# WattMeter-PowerSocket-Controller_V0_100.net
KiCad netlist of a schematic drawn in EAGLE
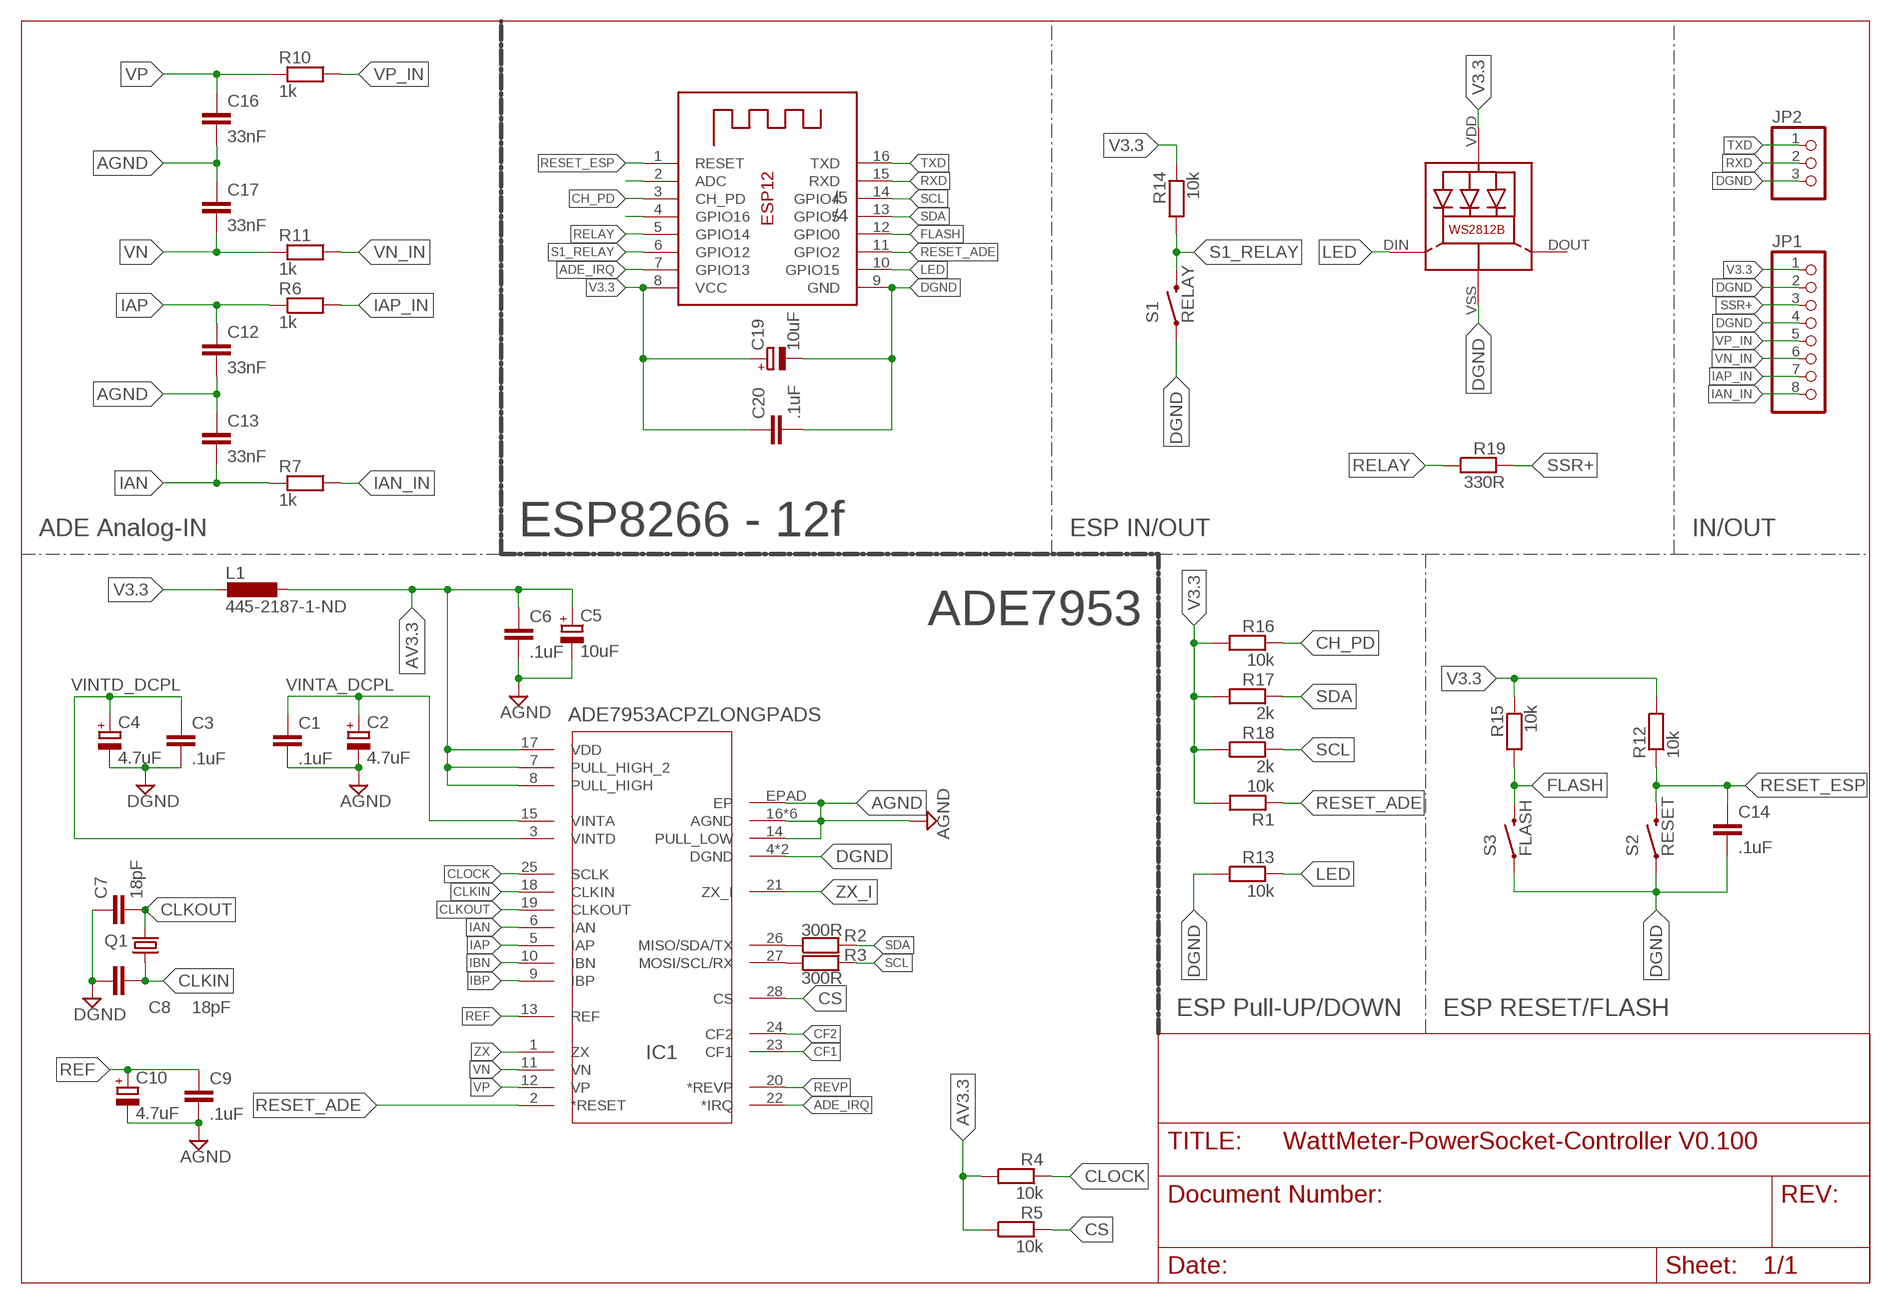
[diagram p0: schematic, sheet 1]

(export (version "E")
  (design (tool "Eeschema 10.0.6"))
  (components
    (comp (ref "C1")
      (value ".1uF")
      (footprint "eagle-import:C0805K@1")
      (libsource (lib "eagle-import") (part "C-EUC0805K"))
    )
    (comp (ref "C2")
      (value "4.7uF")
      (footprint "eagle-import:A_3216-18R")
      (libsource (lib "eagle-import") (part "CPOL-EUA/3216-18R"))
    )
    (comp (ref "C3")
      (value ".1uF")
      (footprint "eagle-import:C0805K@1")
      (libsource (lib "eagle-import") (part "C-EUC0805K"))
    )
    (comp (ref "C4")
      (value "4.7uF")
      (footprint "eagle-import:A_3216-18R")
      (libsource (lib "eagle-import") (part "CPOL-EUA/3216-18R"))
    )
    (comp (ref "C5")
      (value "10uF")
      (footprint "eagle-import:A_3216-18R")
      (libsource (lib "eagle-import") (part "CPOL-EUA/3216-18R"))
    )
    (comp (ref "C6")
      (value ".1uF")
      (footprint "eagle-import:C0805K@1")
      (libsource (lib "eagle-import") (part "C-EUC0805K"))
    )
    (comp (ref "C7")
      (value "18pF")
      (footprint "eagle-import:C0805K@1")
      (libsource (lib "eagle-import") (part "C-EUC0805K"))
    )
    (comp (ref "C8")
      (value "18pF")
      (footprint "eagle-import:C0805K@1")
      (libsource (lib "eagle-import") (part "C-EUC0805K"))
    )
    (comp (ref "C9")
      (value ".1uF")
      (footprint "eagle-import:C0805K@1")
      (libsource (lib "eagle-import") (part "C-EUC0805K"))
    )
    (comp (ref "C10")
      (value "4.7uF")
      (footprint "eagle-import:A_3216-18R")
      (libsource (lib "eagle-import") (part "CPOL-EUA/3216-18R"))
    )
    (comp (ref "C12")
      (value "33nF")
      (footprint "eagle-import:C0805K@1")
      (libsource (lib "eagle-import") (part "C-EUC0805K"))
    )
    (comp (ref "C13")
      (value "33nF")
      (footprint "eagle-import:C0805K@1")
      (libsource (lib "eagle-import") (part "C-EUC0805K"))
    )
    (comp (ref "C14")
      (value ".1uF")
      (footprint "eagle-import:C0805K@1")
      (libsource (lib "eagle-import") (part "C-EUC0805K"))
    )
    (comp (ref "C16")
      (value "33nF")
      (footprint "eagle-import:C0805K@1")
      (libsource (lib "eagle-import") (part "C-EUC0805K"))
    )
    (comp (ref "C17")
      (value "33nF")
      (footprint "eagle-import:C0805K@1")
      (libsource (lib "eagle-import") (part "C-EUC0805K"))
    )
    (comp (ref "C19")
      (value "10uF")
      (footprint "eagle-import:A_3216-18R")
      (libsource (lib "eagle-import") (part "CPOL-EUA/3216-18R"))
    )
    (comp (ref "C20")
      (value ".1uF")
      (footprint "eagle-import:C0805K@1")
      (libsource (lib "eagle-import") (part "C-EUC0805K"))
    )
    (comp (ref "IC1")
      (value "ADE7953ACPZLONGPADS")
      (footprint "eagle-import:VQFN-28-D")
      (libsource (lib "eagle-import") (part "ADE7953ACPZ5.0"))
    )
    (comp (ref "JP1")
      (value "PINHD-1X8")
      (footprint "eagle-import:1X08")
      (libsource (lib "eagle-import") (part "PINHD-1X8"))
    )
    (comp (ref "JP2")
      (value "PINHD-1X3")
      (footprint "eagle-import:1X03")
      (libsource (lib "eagle-import") (part "PINHD-1X3"))
    )
    (comp (ref "L1")
      (value "445-2187-1-ND")
      (footprint "eagle-import:L2012C")
      (libsource (lib "eagle-import") (part "L-EUL2012C"))
    )
    (comp (ref "LED1")
      (value "WS2812B")
      (footprint "eagle-import:WS2812B")
      (libsource (lib "eagle-import") (part "WS2812B"))
    )
    (comp (ref "Q1")
      (value "535-10200-1-ND")
      (footprint "eagle-import:SM49")
      (libsource (lib "eagle-import") (part "CRYSTALSM49"))
    )
    (comp (ref "R1")
      (value "10k")
      (footprint "eagle-import:R0805@1")
      (libsource (lib "eagle-import") (part "R-US_R0805"))
    )
    (comp (ref "R2")
      (value "300R")
      (footprint "eagle-import:R0805@1")
      (libsource (lib "eagle-import") (part "R-US_R0805"))
    )
    (comp (ref "R3")
      (value "300R")
      (footprint "eagle-import:R0805@1")
      (libsource (lib "eagle-import") (part "R-US_R0805"))
    )
    (comp (ref "R4")
      (value "10k")
      (footprint "eagle-import:R0805@1")
      (libsource (lib "eagle-import") (part "R-US_R0805"))
    )
    (comp (ref "R5")
      (value "10k")
      (footprint "eagle-import:R0805@1")
      (libsource (lib "eagle-import") (part "R-US_R0805"))
    )
    (comp (ref "R6")
      (value "1k")
      (footprint "eagle-import:R0805@1")
      (libsource (lib "eagle-import") (part "R-US_R0805"))
    )
    (comp (ref "R7")
      (value "1k")
      (footprint "eagle-import:R0805@1")
      (libsource (lib "eagle-import") (part "R-US_R0805"))
    )
    (comp (ref "R10")
      (value "1k")
      (footprint "eagle-import:R0805@1")
      (libsource (lib "eagle-import") (part "R-US_R0805"))
    )
    (comp (ref "R11")
      (value "1k")
      (footprint "eagle-import:R0805@1")
      (libsource (lib "eagle-import") (part "R-US_R0805"))
    )
    (comp (ref "R12")
      (value "10k")
      (footprint "eagle-import:R0805@1")
      (libsource (lib "eagle-import") (part "R-US_R0805"))
    )
    (comp (ref "R13")
      (value "10k")
      (footprint "eagle-import:R0805@1")
      (libsource (lib "eagle-import") (part "R-US_R0805"))
    )
    (comp (ref "R14")
      (value "10k")
      (footprint "eagle-import:R0805@1")
      (libsource (lib "eagle-import") (part "R-US_R0805"))
    )
    (comp (ref "R15")
      (value "10k")
      (footprint "eagle-import:R0805@1")
      (libsource (lib "eagle-import") (part "R-US_R0805"))
    )
    (comp (ref "R16")
      (value "10k")
      (footprint "eagle-import:R0805@1")
      (libsource (lib "eagle-import") (part "R-US_R0805"))
    )
    (comp (ref "R17")
      (value "2k")
      (footprint "eagle-import:R0805@1")
      (libsource (lib "eagle-import") (part "R-US_R0805"))
    )
    (comp (ref "R18")
      (value "2k")
      (footprint "eagle-import:R0805@1")
      (libsource (lib "eagle-import") (part "R-US_R0805"))
    )
    (comp (ref "R19")
      (value "330R")
      (footprint "eagle-import:R0805@1")
      (libsource (lib "eagle-import") (part "R-US_R0805"))
    )
    (comp (ref "S1")
      (value "RELAY")
      (footprint "eagle-import:TACTILE-SWITCH-SMD")
      (libsource (lib "eagle-import") (part "SWITCH-MOMENTARY-2SMD"))
    )
    (comp (ref "S2")
      (value "RESET")
      (footprint "eagle-import:TACTILE-SWITCH-1101NE")
      (libsource (lib "eagle-import") (part "SWITCH-MOMENTARY-2SMD-1101NE"))
    )
    (comp (ref "S3")
      (value "FLASH")
      (footprint "eagle-import:TACTILE-SWITCH-1101NE")
      (libsource (lib "eagle-import") (part "SWITCH-MOMENTARY-2SMD-1101NE"))
    )
    (comp (ref "X1")
      (value "ESP-12")
      (footprint "eagle-import:ESP-12")
      (libsource (lib "eagle-import") (part "ESP-12"))
    )
  )
  (nets
    (net (code "1") (name "/VINTA_DCPL") (class "Default")
      (node (ref "C1") (pin "1") (pinfunction "1_1") (pintype "passive"))
      (node (ref "C2") (pin "+") (pinfunction "+_+") (pintype "passive"))
      (node (ref "IC1") (pin "15") (pinfunction "VINTA_15") (pintype "passive"))
    )
    (net (code "2") (name "/VINTD_DCPL") (class "Default")
      (node (ref "C3") (pin "1") (pinfunction "1_1") (pintype "passive"))
      (node (ref "C4") (pin "+") (pinfunction "+_+") (pintype "passive"))
      (node (ref "IC1") (pin "3") (pinfunction "VINTD_3") (pintype "passive"))
    )
    (net (code "3") (name "ADE_IRQ") (class "Default")
      (node (ref "IC1") (pin "22") (pinfunction "*IRQ_22") (pintype "passive"))
      (node (ref "X1") (pin "7") (pinfunction "GPIO13_7") (pintype "bidirectional"))
    )
    (net (code "4") (name "AGND") (class "Default")
      (node (ref "C1") (pin "2") (pinfunction "2_2") (pintype "passive"))
      (node (ref "C10") (pin "-") (pinfunction "-_-") (pintype "passive"))
      (node (ref "C12") (pin "2") (pinfunction "2_2") (pintype "passive"))
      (node (ref "C13") (pin "1") (pinfunction "1_1") (pintype "passive"))
      (node (ref "C16") (pin "2") (pinfunction "2_2") (pintype "passive"))
      (node (ref "C17") (pin "1") (pinfunction "1_1") (pintype "passive"))
      (node (ref "C2") (pin "-") (pinfunction "-_-") (pintype "passive"))
      (node (ref "C5") (pin "-") (pinfunction "-_-") (pintype "passive"))
      (node (ref "C6") (pin "2") (pinfunction "2_2") (pintype "passive"))
      (node (ref "C9") (pin "2") (pinfunction "2_2") (pintype "passive"))
      (node (ref "IC1") (pin "14") (pinfunction "PULL_LOW_14") (pintype "passive"))
      (node (ref "IC1") (pin "16") (pinfunction "AGND_16") (pintype "passive"))
      (node (ref "IC1") (pin "29") (pinfunction "AGND_29") (pintype "passive"))
      (node (ref "IC1") (pin "30") (pinfunction "AGND_30") (pintype "passive"))
      (node (ref "IC1") (pin "31") (pinfunction "AGND_31") (pintype "passive"))
      (node (ref "IC1") (pin "32") (pinfunction "AGND_32") (pintype "passive"))
      (node (ref "IC1") (pin "EPAD") (pinfunction "EP_EPAD") (pintype "passive"))
      (node (ref "IC1") (pin "_AGND") (pinfunction "AGND__AGND") (pintype "passive"))
    )
    (net (code "5") (name "AV3.3") (class "Default")
      (node (ref "C5") (pin "+") (pinfunction "+_+") (pintype "passive"))
      (node (ref "C6") (pin "1") (pinfunction "1_1") (pintype "passive"))
      (node (ref "IC1") (pin "17") (pinfunction "VDD_17") (pintype "passive"))
      (node (ref "IC1") (pin "7") (pinfunction "PULL_HIGH_2_7") (pintype "passive"))
      (node (ref "IC1") (pin "8") (pinfunction "PULL_HIGH_8") (pintype "passive"))
      (node (ref "L1") (pin "1") (pinfunction "1_1") (pintype "passive"))
      (node (ref "R4") (pin "2") (pinfunction "2_2") (pintype "passive"))
      (node (ref "R5") (pin "2") (pinfunction "2_2") (pintype "passive"))
    )
    (net (code "6") (name "CF1") (class "Default")
      (node (ref "IC1") (pin "23") (pinfunction "CF1_23") (pintype "passive"))
    )
    (net (code "7") (name "CF2") (class "Default")
      (node (ref "IC1") (pin "24") (pinfunction "CF2_24") (pintype "passive"))
    )
    (net (code "8") (name "CH_PD") (class "Default")
      (node (ref "R16") (pin "1") (pinfunction "1_1") (pintype "passive"))
      (node (ref "X1") (pin "3") (pinfunction "CH_PD_3") (pintype "input"))
    )
    (net (code "9") (name "CLKIN") (class "Default")
      (node (ref "C8") (pin "2") (pinfunction "2_2") (pintype "passive"))
      (node (ref "IC1") (pin "18") (pinfunction "CLKIN_18") (pintype "passive"))
      (node (ref "Q1") (pin "1") (pinfunction "1_1") (pintype "passive"))
    )
    (net (code "10") (name "CLKOUT") (class "Default")
      (node (ref "C7") (pin "2") (pinfunction "2_2") (pintype "passive"))
      (node (ref "IC1") (pin "19") (pinfunction "CLKOUT_19") (pintype "passive"))
      (node (ref "Q1") (pin "2") (pinfunction "2_2") (pintype "passive"))
    )
    (net (code "11") (name "CLOCK") (class "Default")
      (node (ref "IC1") (pin "25") (pinfunction "SCLK_25") (pintype "passive"))
      (node (ref "R4") (pin "1") (pinfunction "1_1") (pintype "passive"))
    )
    (net (code "12") (name "CS") (class "Default")
      (node (ref "IC1") (pin "28") (pinfunction "CS_28") (pintype "passive"))
      (node (ref "R5") (pin "1") (pinfunction "1_1") (pintype "passive"))
    )
    (net (code "13") (name "DGND") (class "Default")
      (node (ref "C14") (pin "2") (pinfunction "2_2") (pintype "passive"))
      (node (ref "C19") (pin "-") (pinfunction "-_-") (pintype "passive"))
      (node (ref "C20") (pin "2") (pinfunction "2_2") (pintype "passive"))
      (node (ref "C3") (pin "2") (pinfunction "2_2") (pintype "passive"))
      (node (ref "C4") (pin "-") (pinfunction "-_-") (pintype "passive"))
      (node (ref "C7") (pin "1") (pinfunction "1_1") (pintype "passive"))
      (node (ref "C8") (pin "1") (pinfunction "1_1") (pintype "passive"))
      (node (ref "IC1") (pin "4") (pinfunction "DGND_4") (pintype "passive"))
      (node (ref "IC1") (pin "_DGND") (pinfunction "DGND__DGND") (pintype "passive"))
      (node (ref "JP1") (pin "2") (pinfunction "2_2") (pintype "passive"))
      (node (ref "JP1") (pin "4") (pinfunction "4_4") (pintype "passive"))
      (node (ref "JP2") (pin "3") (pinfunction "3_3") (pintype "passive"))
      (node (ref "LED1") (pin "VSS") (pinfunction "GND_VSS") (pintype "power_in"))
      (node (ref "R13") (pin "2") (pinfunction "2_2") (pintype "passive"))
      (node (ref "S1") (pin "1") (pinfunction "1_1") (pintype "passive"))
      (node (ref "S2") (pin "1") (pinfunction "1_1") (pintype "passive"))
      (node (ref "S3") (pin "1") (pinfunction "1_1") (pintype "passive"))
      (node (ref "X1") (pin "9") (pinfunction "GND_9") (pintype "power_in"))
    )
    (net (code "14") (name "FLASH") (class "Default")
      (node (ref "R15") (pin "2") (pinfunction "2_2") (pintype "passive"))
      (node (ref "S3") (pin "2") (pinfunction "2_2") (pintype "passive"))
      (node (ref "X1") (pin "12") (pinfunction "GPIO0_12") (pintype "bidirectional"))
    )
    (net (code "15") (name "IAN") (class "Default")
      (node (ref "C13") (pin "2") (pinfunction "2_2") (pintype "passive"))
      (node (ref "IC1") (pin "6") (pinfunction "IAN_6") (pintype "passive"))
      (node (ref "R7") (pin "1") (pinfunction "1_1") (pintype "passive"))
    )
    (net (code "16") (name "IAN_IN") (class "Default")
      (node (ref "JP1") (pin "8") (pinfunction "8_8") (pintype "passive"))
      (node (ref "R7") (pin "2") (pinfunction "2_2") (pintype "passive"))
    )
    (net (code "17") (name "IAP") (class "Default")
      (node (ref "C12") (pin "1") (pinfunction "1_1") (pintype "passive"))
      (node (ref "IC1") (pin "5") (pinfunction "IAP_5") (pintype "passive"))
      (node (ref "R6") (pin "1") (pinfunction "1_1") (pintype "passive"))
    )
    (net (code "18") (name "IAP_IN") (class "Default")
      (node (ref "JP1") (pin "7") (pinfunction "7_7") (pintype "passive"))
      (node (ref "R6") (pin "2") (pinfunction "2_2") (pintype "passive"))
    )
    (net (code "19") (name "IBN") (class "Default")
      (node (ref "IC1") (pin "10") (pinfunction "IBN_10") (pintype "passive"))
    )
    (net (code "20") (name "IBP") (class "Default")
      (node (ref "IC1") (pin "9") (pinfunction "IBP_9") (pintype "passive"))
    )
    (net (code "21") (name "LED") (class "Default")
      (node (ref "LED1") (pin "DIN") (pinfunction "DI_DIN") (pintype "input"))
      (node (ref "R13") (pin "1") (pinfunction "1_1") (pintype "passive"))
      (node (ref "X1") (pin "10") (pinfunction "GPIO15_10") (pintype "bidirectional"))
    )
    (net (code "22") (name "Net-(IC1-MISO{slash}SDA{slash}TX)") (class "Default")
      (node (ref "IC1") (pin "26") (pinfunction "MISO/SDA/TX_26") (pintype "passive"))
      (node (ref "R2") (pin "1") (pinfunction "1_1") (pintype "passive"))
    )
    (net (code "23") (name "Net-(IC1-MOSI{slash}SCL{slash}RX)") (class "Default")
      (node (ref "IC1") (pin "27") (pinfunction "MOSI/SCL/RX_27") (pintype "passive"))
      (node (ref "R3") (pin "1") (pinfunction "1_1") (pintype "passive"))
    )
    (net (code "24") (name "REF") (class "Default")
      (node (ref "C10") (pin "+") (pinfunction "+_+") (pintype "passive"))
      (node (ref "C9") (pin "1") (pinfunction "1_1") (pintype "passive"))
      (node (ref "IC1") (pin "13") (pinfunction "REF_13") (pintype "passive"))
    )
    (net (code "25") (name "RELAY") (class "Default")
      (node (ref "R19") (pin "2") (pinfunction "2_2") (pintype "passive"))
      (node (ref "X1") (pin "5") (pinfunction "GPIO14_5") (pintype "bidirectional"))
    )
    (net (code "26") (name "RESET_ADE") (class "Default")
      (node (ref "IC1") (pin "2") (pinfunction "*RESET_2") (pintype "passive"))
      (node (ref "R1") (pin "1") (pinfunction "1_1") (pintype "passive"))
      (node (ref "X1") (pin "11") (pinfunction "GPIO2_11") (pintype "bidirectional"))
    )
    (net (code "27") (name "RESET_ESP") (class "Default")
      (node (ref "C14") (pin "1") (pinfunction "1_1") (pintype "passive"))
      (node (ref "R12") (pin "1") (pinfunction "1_1") (pintype "passive"))
      (node (ref "S2") (pin "2") (pinfunction "2_2") (pintype "passive"))
      (node (ref "X1") (pin "1") (pinfunction "RESET_1") (pintype "input"))
    )
    (net (code "28") (name "REVP") (class "Default")
      (node (ref "IC1") (pin "20") (pinfunction "*REVP_20") (pintype "passive"))
    )
    (net (code "29") (name "RXD") (class "Default")
      (node (ref "JP2") (pin "2") (pinfunction "2_2") (pintype "passive"))
      (node (ref "X1") (pin "15") (pinfunction "RXD_15") (pintype "input"))
    )
    (net (code "30") (name "S1_RELAY") (class "Default")
      (node (ref "R14") (pin "2") (pinfunction "2_2") (pintype "passive"))
      (node (ref "S1") (pin "3") (pinfunction "2_3") (pintype "passive"))
      (node (ref "X1") (pin "6") (pinfunction "GPIO12_6") (pintype "bidirectional"))
    )
    (net (code "31") (name "SCL") (class "Default")
      (node (ref "R18") (pin "1") (pinfunction "1_1") (pintype "passive"))
      (node (ref "R3") (pin "2") (pinfunction "2_2") (pintype "passive"))
      (node (ref "X1") (pin "14") (pinfunction "GPIO4_14") (pintype "bidirectional"))
    )
    (net (code "32") (name "SDA") (class "Default")
      (node (ref "R17") (pin "1") (pinfunction "1_1") (pintype "passive"))
      (node (ref "R2") (pin "2") (pinfunction "2_2") (pintype "passive"))
      (node (ref "X1") (pin "13") (pinfunction "GPIO5_13") (pintype "bidirectional"))
    )
    (net (code "33") (name "SSR+") (class "Default")
      (node (ref "JP1") (pin "3") (pinfunction "3_3") (pintype "passive"))
      (node (ref "R19") (pin "1") (pinfunction "1_1") (pintype "passive"))
    )
    (net (code "34") (name "TXD") (class "Default")
      (node (ref "JP2") (pin "1") (pinfunction "1_1") (pintype "passive"))
      (node (ref "X1") (pin "16") (pinfunction "TXD_16") (pintype "output"))
    )
    (net (code "35") (name "V3.3") (class "Default")
      (node (ref "C19") (pin "+") (pinfunction "+_+") (pintype "passive"))
      (node (ref "C20") (pin "1") (pinfunction "1_1") (pintype "passive"))
      (node (ref "JP1") (pin "1") (pinfunction "1_1") (pintype "passive"))
      (node (ref "L1") (pin "2") (pinfunction "2_2") (pintype "passive"))
      (node (ref "LED1") (pin "VDD") (pinfunction "VDD_VDD") (pintype "power_in"))
      (node (ref "R1") (pin "2") (pinfunction "2_2") (pintype "passive"))
      (node (ref "R12") (pin "2") (pinfunction "2_2") (pintype "passive"))
      (node (ref "R14") (pin "1") (pinfunction "1_1") (pintype "passive"))
      (node (ref "R15") (pin "1") (pinfunction "1_1") (pintype "passive"))
      (node (ref "R16") (pin "2") (pinfunction "2_2") (pintype "passive"))
      (node (ref "R17") (pin "2") (pinfunction "2_2") (pintype "passive"))
      (node (ref "R18") (pin "2") (pinfunction "2_2") (pintype "passive"))
      (node (ref "X1") (pin "8") (pinfunction "VCC_8") (pintype "power_in"))
    )
    (net (code "36") (name "VN") (class "Default")
      (node (ref "C17") (pin "2") (pinfunction "2_2") (pintype "passive"))
      (node (ref "IC1") (pin "11") (pinfunction "VN_11") (pintype "passive"))
      (node (ref "R11") (pin "1") (pinfunction "1_1") (pintype "passive"))
    )
    (net (code "37") (name "VN_IN") (class "Default")
      (node (ref "JP1") (pin "6") (pinfunction "6_6") (pintype "passive"))
      (node (ref "R11") (pin "2") (pinfunction "2_2") (pintype "passive"))
    )
    (net (code "38") (name "VP") (class "Default")
      (node (ref "C16") (pin "1") (pinfunction "1_1") (pintype "passive"))
      (node (ref "IC1") (pin "12") (pinfunction "VP_12") (pintype "passive"))
      (node (ref "R10") (pin "1") (pinfunction "1_1") (pintype "passive"))
    )
    (net (code "39") (name "VP_IN") (class "Default")
      (node (ref "JP1") (pin "5") (pinfunction "5_5") (pintype "passive"))
      (node (ref "R10") (pin "2") (pinfunction "2_2") (pintype "passive"))
    )
    (net (code "40") (name "ZX") (class "Default")
      (node (ref "IC1") (pin "1") (pinfunction "ZX_1") (pintype "passive"))
    )
    (net (code "41") (name "ZX_I") (class "Default")
      (node (ref "IC1") (pin "21") (pinfunction "ZX_I_21") (pintype "passive"))
    )
    (net (code "42") (name "unconnected-(LED1-DO-PadDOUT)") (class "Default")
      (node (ref "LED1") (pin "DOUT") (pinfunction "DO_DOUT") (pintype "output"))
    )
    (net (code "43") (name "unconnected-(X1-ADC-Pad2)") (class "Default")
      (node (ref "X1") (pin "2") (pinfunction "ADC_2") (pintype "passive"))
    )
    (net (code "44") (name "unconnected-(X1-GPIO16-Pad4)") (class "Default")
      (node (ref "X1") (pin "4") (pinfunction "GPIO16_4") (pintype "bidirectional"))
    )
  )
)
